# d_00_e_03.net
KiCad netlist of a schematic drawn in EasyEDA
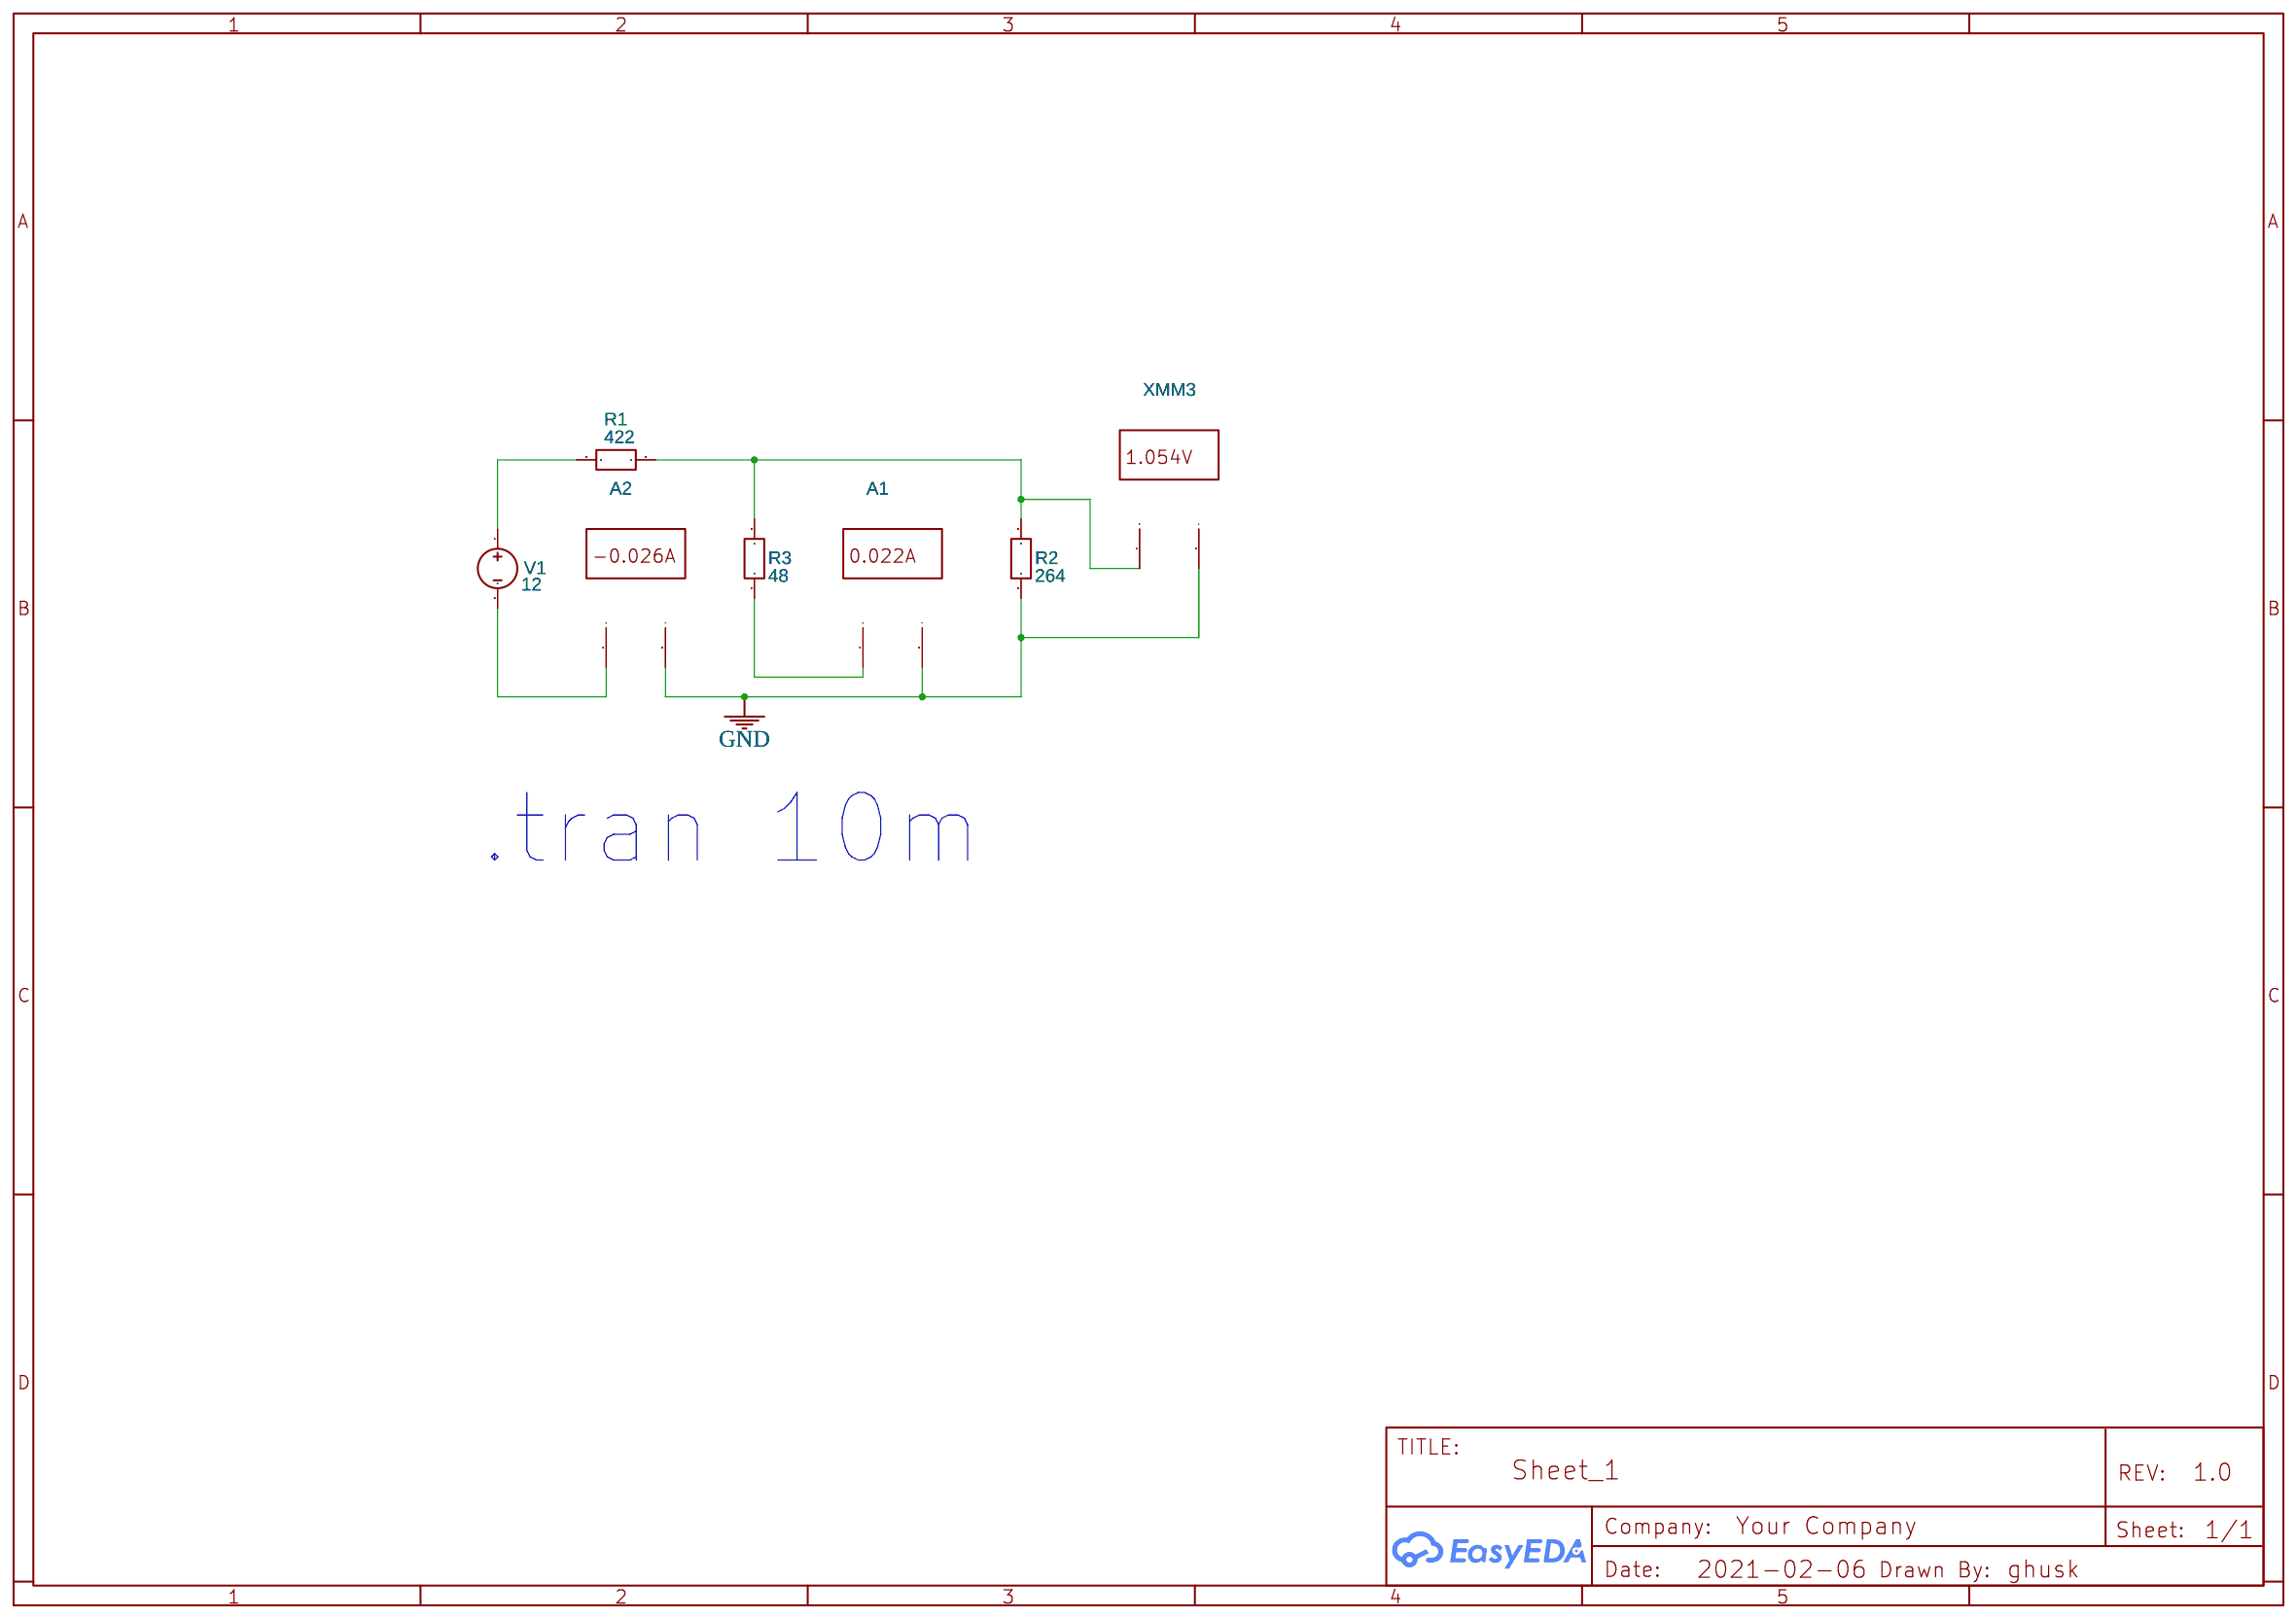
[diagram p0: schematic sheet]

(export (version "E")
  (design (tool "Eeschema 10.0.6"))
  (components
    (comp (ref "A1") (value "Multimeter") (libsource (lib "") (part "MULTIMETER_2")))
    (comp (ref "A2") (value "Multimeter") (libsource (lib "") (part "MULTIMETER_1")))
    (comp (ref "R1") (value "422") (libsource (lib "") (part "Resistor_EU_1")))
    (comp (ref "R2") (value "264") (libsource (lib "") (part "Resistor_EU")))
    (comp (ref "R3") (value "48") (libsource (lib "") (part "Resistor_EU")))
    (comp (ref "V1") (value "12") (libsource (lib "") (part "VDC")))
    (comp (ref "XMM3") (value "Multimeter") (libsource (lib "") (part "MULTIMETER")))
  )
  (nets
    (net (code "1") (name "GND") (class "Default")
      (node (ref "A1") (pin "2") (pinfunction "I_2") (pintype "unspecified"))
      (node (ref "A2") (pin "2") (pinfunction "I_2") (pintype "unspecified"))
      (node (ref "R2") (pin "1") (pinfunction "1_1") (pintype "unspecified"))
      (node (ref "XMM3") (pin "2") (pinfunction "I_2") (pintype "unspecified"))
    )
    (net (code "2") (name "Net-(A1-+)") (class "Default")
      (node (ref "A1") (pin "1") (pinfunction "+_1") (pintype "unspecified"))
      (node (ref "R3") (pin "1") (pinfunction "1_1") (pintype "unspecified"))
    )
    (net (code "3") (name "Net-(A2-+)") (class "Default")
      (node (ref "A2") (pin "1") (pinfunction "+_1") (pintype "unspecified"))
      (node (ref "V1") (pin "2") (pinfunction "2_2") (pintype "unspecified"))
    )
    (net (code "4") (name "Net-(R1-Pad1)") (class "Default")
      (node (ref "R1") (pin "1") (pinfunction "1_1") (pintype "unspecified"))
      (node (ref "V1") (pin "1") (pinfunction "1_1") (pintype "unspecified"))
    )
    (net (code "5") (name "Net-(XMM3-+)") (class "Default")
      (node (ref "R1") (pin "2") (pinfunction "2_2") (pintype "unspecified"))
      (node (ref "R2") (pin "2") (pinfunction "2_2") (pintype "unspecified"))
      (node (ref "R3") (pin "2") (pinfunction "2_2") (pintype "unspecified"))
      (node (ref "XMM3") (pin "1") (pinfunction "+_1") (pintype "unspecified"))
    )
  )
)
